# Dual_linear_VCA_chip_v2_0.net
KiCad netlist of a schematic drawn in EAGLE
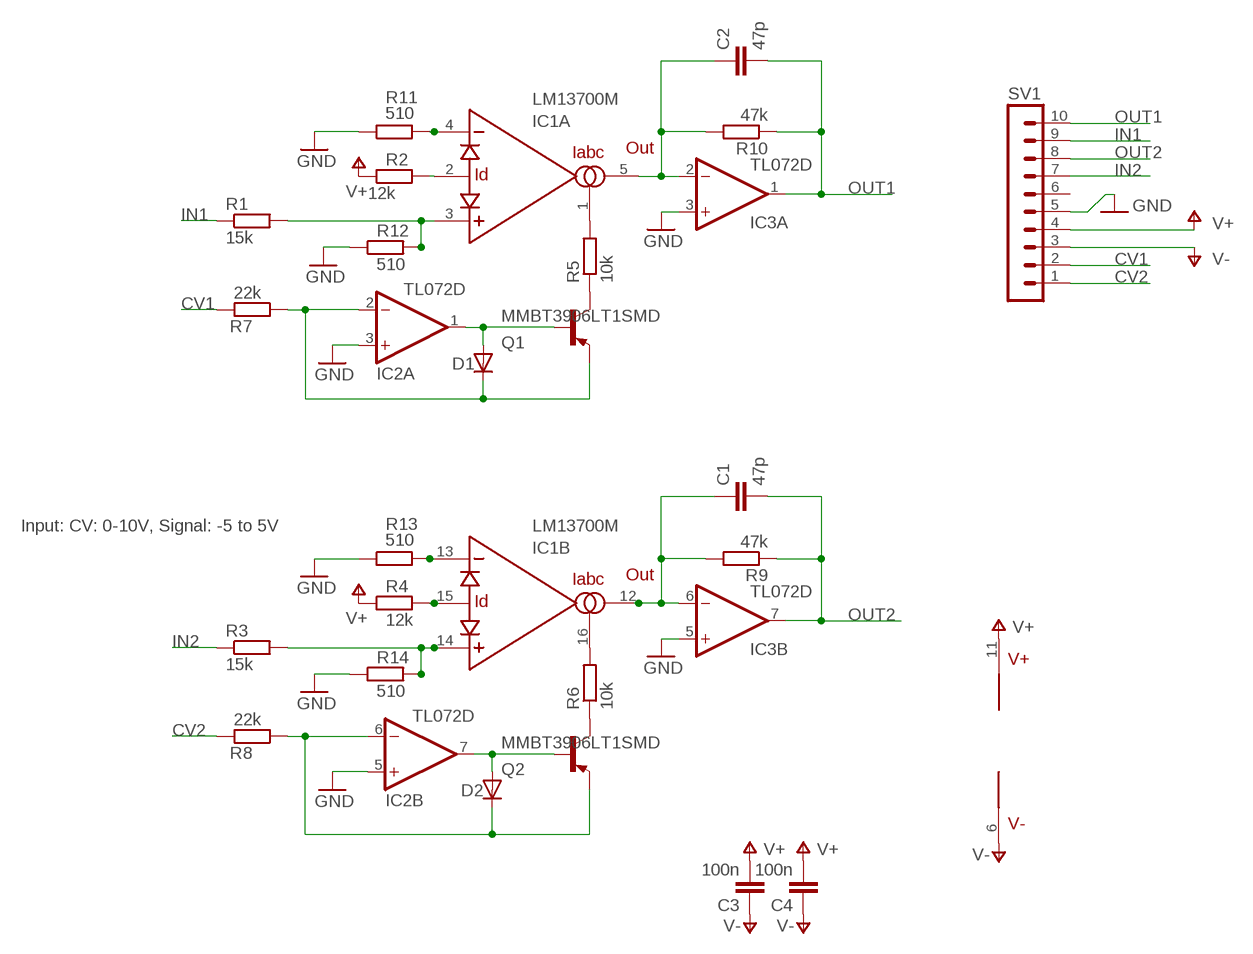
[diagram p0: schematic, sheet 1]

(export (version "E")
  (design (tool "Eeschema 10.0.6"))
  (components
    (comp (ref "C1")
      (value "47p")
      (footprint "eagle-import:C0805")
      (libsource (lib "eagle-import") (part "C-EUC0805"))
    )
    (comp (ref "C2")
      (value "47p")
      (footprint "eagle-import:C0805")
      (libsource (lib "eagle-import") (part "C-EUC0805"))
    )
    (comp (ref "C3")
      (value "100n")
      (footprint "eagle-import:C0805")
      (libsource (lib "eagle-import") (part "C-EUC0805"))
    )
    (comp (ref "C4")
      (value "100n")
      (footprint "eagle-import:C0805")
      (libsource (lib "eagle-import") (part "C-EUC0805"))
    )
    (comp (ref "D1")
      (value "DIODE-SOD80C")
      (footprint "eagle-import:SOD80C")
      (libsource (lib "eagle-import") (part "DIODE-SOD80C"))
    )
    (comp (ref "D2")
      (value "DIODE-SOD80C")
      (footprint "eagle-import:SOD80C")
      (libsource (lib "eagle-import") (part "DIODE-SOD80C"))
    )
    (comp (ref "IC1")
      (value "LM13700M")
      (footprint "eagle-import:SO16")
      (libsource (lib "eagle-import") (part "LM13700M"))
    )
    (comp (ref "IC2")
      (value "TL072D")
      (footprint "eagle-import:SO08")
      (libsource (lib "eagle-import") (part "TL072D"))
    )
    (comp (ref "IC3")
      (value "TL072D")
      (footprint "eagle-import:SO08")
      (libsource (lib "eagle-import") (part "TL072D"))
    )
    (comp (ref "Q1")
      (value "MMBT3906LT1SMD")
      (footprint "eagle-import:SOT23-BEC")
      (libsource (lib "eagle-import") (part "MMBT3906SMDLT1"))
    )
    (comp (ref "Q2")
      (value "MMBT3906LT1SMD")
      (footprint "eagle-import:SOT23-BEC")
      (libsource (lib "eagle-import") (part "MMBT3906SMDLT1"))
    )
    (comp (ref "R1")
      (value "15k")
      (footprint "eagle-import:R0805")
      (libsource (lib "eagle-import") (part "R-EU_R0805"))
    )
    (comp (ref "R2")
      (value "12k")
      (footprint "eagle-import:R0805")
      (libsource (lib "eagle-import") (part "R-EU_R0805"))
    )
    (comp (ref "R3")
      (value "15k")
      (footprint "eagle-import:R0805")
      (libsource (lib "eagle-import") (part "R-EU_R0805"))
    )
    (comp (ref "R4")
      (value "12k")
      (footprint "eagle-import:R0805")
      (libsource (lib "eagle-import") (part "R-EU_R0805"))
    )
    (comp (ref "R5")
      (value "10k")
      (footprint "eagle-import:R0805")
      (libsource (lib "eagle-import") (part "R-EU_R0805"))
    )
    (comp (ref "R6")
      (value "10k")
      (footprint "eagle-import:R0805")
      (libsource (lib "eagle-import") (part "R-EU_R0805"))
    )
    (comp (ref "R7")
      (value "22k")
      (footprint "eagle-import:R0805")
      (libsource (lib "eagle-import") (part "R-EU_R0805"))
    )
    (comp (ref "R8")
      (value "22k")
      (footprint "eagle-import:R0805")
      (libsource (lib "eagle-import") (part "R-EU_R0805"))
    )
    (comp (ref "R9")
      (value "47k")
      (footprint "eagle-import:R0805")
      (libsource (lib "eagle-import") (part "R-EU_R0805"))
    )
    (comp (ref "R10")
      (value "47k")
      (footprint "eagle-import:R0805")
      (libsource (lib "eagle-import") (part "R-EU_R0805"))
    )
    (comp (ref "R11")
      (value "510")
      (footprint "eagle-import:R0805")
      (libsource (lib "eagle-import") (part "R-EU_R0805"))
    )
    (comp (ref "R12")
      (value "510")
      (footprint "eagle-import:R0805")
      (libsource (lib "eagle-import") (part "R-EU_R0805"))
    )
    (comp (ref "R13")
      (value "510")
      (footprint "eagle-import:R0805")
      (libsource (lib "eagle-import") (part "R-EU_R0805"))
    )
    (comp (ref "R14")
      (value "510")
      (footprint "eagle-import:R0805")
      (libsource (lib "eagle-import") (part "R-EU_R0805"))
    )
    (comp (ref "SV1")
      (value "MA10-1")
      (footprint "eagle-import:MA10-1")
      (libsource (lib "eagle-import") (part "MA10-1"))
    )
  )
  (nets
    (net (code "1") (name "/CV1") (class "Default")
      (node (ref "R7") (pin "2") (pinfunction "2_2") (pintype "passive"))
      (node (ref "SV1") (pin "2") (pinfunction "2_2") (pintype "passive"))
    )
    (net (code "2") (name "/CV2") (class "Default")
      (node (ref "R8") (pin "2") (pinfunction "2_2") (pintype "passive"))
      (node (ref "SV1") (pin "1") (pinfunction "1_1") (pintype "passive"))
    )
    (net (code "3") (name "/IN1") (class "Default")
      (node (ref "R1") (pin "1") (pinfunction "1_1") (pintype "passive"))
      (node (ref "SV1") (pin "9") (pinfunction "9_9") (pintype "passive"))
    )
    (net (code "4") (name "/IN2") (class "Default")
      (node (ref "R3") (pin "1") (pinfunction "1_1") (pintype "passive"))
      (node (ref "SV1") (pin "7") (pinfunction "7_7") (pintype "passive"))
    )
    (net (code "5") (name "/OUT1") (class "Default")
      (node (ref "C2") (pin "2") (pinfunction "2_2") (pintype "passive"))
      (node (ref "IC3") (pin "1") (pinfunction "OUT_1") (pintype "output"))
      (node (ref "R10") (pin "1") (pinfunction "1_1") (pintype "passive"))
      (node (ref "SV1") (pin "10") (pinfunction "10_10") (pintype "passive"))
    )
    (net (code "6") (name "/OUT2") (class "Default")
      (node (ref "C1") (pin "2") (pinfunction "2_2") (pintype "passive"))
      (node (ref "IC3") (pin "7") (pinfunction "OUT_7") (pintype "output"))
      (node (ref "R9") (pin "1") (pinfunction "1_1") (pintype "passive"))
      (node (ref "SV1") (pin "8") (pinfunction "8_8") (pintype "passive"))
    )
    (net (code "7") (name "GND") (class "Default")
      (node (ref "IC2") (pin "3") (pinfunction "+IN_3") (pintype "input"))
      (node (ref "IC2") (pin "5") (pinfunction "+IN_5") (pintype "input"))
      (node (ref "IC3") (pin "3") (pinfunction "+IN_3") (pintype "input"))
      (node (ref "IC3") (pin "5") (pinfunction "+IN_5") (pintype "input"))
      (node (ref "R11") (pin "1") (pinfunction "1_1") (pintype "passive"))
      (node (ref "R12") (pin "1") (pinfunction "1_1") (pintype "passive"))
      (node (ref "R13") (pin "1") (pinfunction "1_1") (pintype "passive"))
      (node (ref "R14") (pin "1") (pinfunction "1_1") (pintype "passive"))
      (node (ref "SV1") (pin "5") (pinfunction "5_5") (pintype "passive"))
    )
    (net (code "8") (name "Net-(IC1A-+IN)") (class "Default")
      (node (ref "IC1") (pin "3") (pinfunction "+IN_3") (pintype "bidirectional"))
      (node (ref "R1") (pin "2") (pinfunction "2_2") (pintype "passive"))
      (node (ref "R12") (pin "2") (pinfunction "2_2") (pintype "passive"))
    )
    (net (code "9") (name "Net-(IC1A--IN)") (class "Default")
      (node (ref "IC1") (pin "4") (pinfunction "-IN_4") (pintype "bidirectional"))
      (node (ref "R11") (pin "2") (pinfunction "2_2") (pintype "passive"))
    )
    (net (code "10") (name "Net-(IC1A-IABC)") (class "Default")
      (node (ref "IC1") (pin "1") (pinfunction "IABC_1") (pintype "bidirectional"))
      (node (ref "R5") (pin "2") (pinfunction "2_2") (pintype "passive"))
    )
    (net (code "11") (name "Net-(IC1A-ID)") (class "Default")
      (node (ref "IC1") (pin "2") (pinfunction "ID_2") (pintype "bidirectional"))
      (node (ref "R2") (pin "2") (pinfunction "2_2") (pintype "passive"))
    )
    (net (code "12") (name "Net-(IC1A-OUT)") (class "Default")
      (node (ref "C2") (pin "1") (pinfunction "1_1") (pintype "passive"))
      (node (ref "IC1") (pin "5") (pinfunction "OUT_5") (pintype "bidirectional"))
      (node (ref "IC3") (pin "2") (pinfunction "-IN_2") (pintype "input"))
      (node (ref "R10") (pin "2") (pinfunction "2_2") (pintype "passive"))
    )
    (net (code "13") (name "Net-(IC1B-+IN)") (class "Default")
      (node (ref "IC1") (pin "14") (pinfunction "+IN_14") (pintype "bidirectional"))
      (node (ref "R14") (pin "2") (pinfunction "2_2") (pintype "passive"))
      (node (ref "R3") (pin "2") (pinfunction "2_2") (pintype "passive"))
    )
    (net (code "14") (name "Net-(IC1B--IN)") (class "Default")
      (node (ref "IC1") (pin "13") (pinfunction "-IN_13") (pintype "bidirectional"))
      (node (ref "R13") (pin "2") (pinfunction "2_2") (pintype "passive"))
    )
    (net (code "15") (name "Net-(IC1B-IABC)") (class "Default")
      (node (ref "IC1") (pin "16") (pinfunction "IABC_16") (pintype "bidirectional"))
      (node (ref "R6") (pin "2") (pinfunction "2_2") (pintype "passive"))
    )
    (net (code "16") (name "Net-(IC1B-ID)") (class "Default")
      (node (ref "IC1") (pin "15") (pinfunction "ID_15") (pintype "bidirectional"))
      (node (ref "R4") (pin "2") (pinfunction "2_2") (pintype "passive"))
    )
    (net (code "17") (name "Net-(IC1B-OUT)") (class "Default")
      (node (ref "C1") (pin "1") (pinfunction "1_1") (pintype "passive"))
      (node (ref "IC1") (pin "12") (pinfunction "OUT_12") (pintype "bidirectional"))
      (node (ref "IC3") (pin "6") (pinfunction "-IN_6") (pintype "input"))
      (node (ref "R9") (pin "2") (pinfunction "2_2") (pintype "passive"))
    )
    (net (code "18") (name "Net-(IC2A--IN)") (class "Default")
      (node (ref "D1") (pin "C") (pinfunction "C_C") (pintype "passive"))
      (node (ref "IC2") (pin "2") (pinfunction "-IN_2") (pintype "input"))
      (node (ref "Q1") (pin "E") (pinfunction "E_E") (pintype "passive"))
      (node (ref "R7") (pin "1") (pinfunction "1_1") (pintype "passive"))
    )
    (net (code "19") (name "Net-(IC2A-OUT)") (class "Default")
      (node (ref "D1") (pin "A") (pinfunction "A_A") (pintype "passive"))
      (node (ref "IC2") (pin "1") (pinfunction "OUT_1") (pintype "output"))
      (node (ref "Q1") (pin "B") (pinfunction "B_B") (pintype "passive"))
    )
    (net (code "20") (name "Net-(IC2B--IN)") (class "Default")
      (node (ref "D2") (pin "C") (pinfunction "C_C") (pintype "passive"))
      (node (ref "IC2") (pin "6") (pinfunction "-IN_6") (pintype "input"))
      (node (ref "Q2") (pin "E") (pinfunction "E_E") (pintype "passive"))
      (node (ref "R8") (pin "1") (pinfunction "1_1") (pintype "passive"))
    )
    (net (code "21") (name "Net-(IC2B-OUT)") (class "Default")
      (node (ref "D2") (pin "A") (pinfunction "A_A") (pintype "passive"))
      (node (ref "IC2") (pin "7") (pinfunction "OUT_7") (pintype "output"))
      (node (ref "Q2") (pin "B") (pinfunction "B_B") (pintype "passive"))
    )
    (net (code "22") (name "Net-(Q1-PadC)") (class "Default")
      (node (ref "Q1") (pin "C") (pinfunction "C_C") (pintype "passive"))
      (node (ref "R5") (pin "1") (pinfunction "1_1") (pintype "passive"))
    )
    (net (code "23") (name "Net-(Q2-PadC)") (class "Default")
      (node (ref "Q2") (pin "C") (pinfunction "C_C") (pintype "passive"))
      (node (ref "R6") (pin "1") (pinfunction "1_1") (pintype "passive"))
    )
    (net (code "24") (name "V+") (class "Default")
      (node (ref "C3") (pin "2") (pinfunction "2_2") (pintype "passive"))
      (node (ref "C4") (pin "2") (pinfunction "2_2") (pintype "passive"))
      (node (ref "IC1") (pin "11") (pinfunction "V+_11") (pintype "bidirectional"))
      (node (ref "R2") (pin "1") (pinfunction "1_1") (pintype "passive"))
      (node (ref "R4") (pin "1") (pinfunction "1_1") (pintype "passive"))
      (node (ref "SV1") (pin "4") (pinfunction "4_4") (pintype "passive"))
    )
    (net (code "25") (name "V-") (class "Default")
      (node (ref "C3") (pin "1") (pinfunction "1_1") (pintype "passive"))
      (node (ref "C4") (pin "1") (pinfunction "1_1") (pintype "passive"))
      (node (ref "IC1") (pin "6") (pinfunction "V-_6") (pintype "bidirectional"))
      (node (ref "SV1") (pin "3") (pinfunction "3_3") (pintype "passive"))
    )
    (net (code "26") (name "unconnected-(SV1-Pad6)") (class "Default")
      (node (ref "SV1") (pin "6") (pinfunction "6_6") (pintype "passive"))
    )
  )
)
